# rev_D.net
KiCad netlist of a schematic drawn in EAGLE
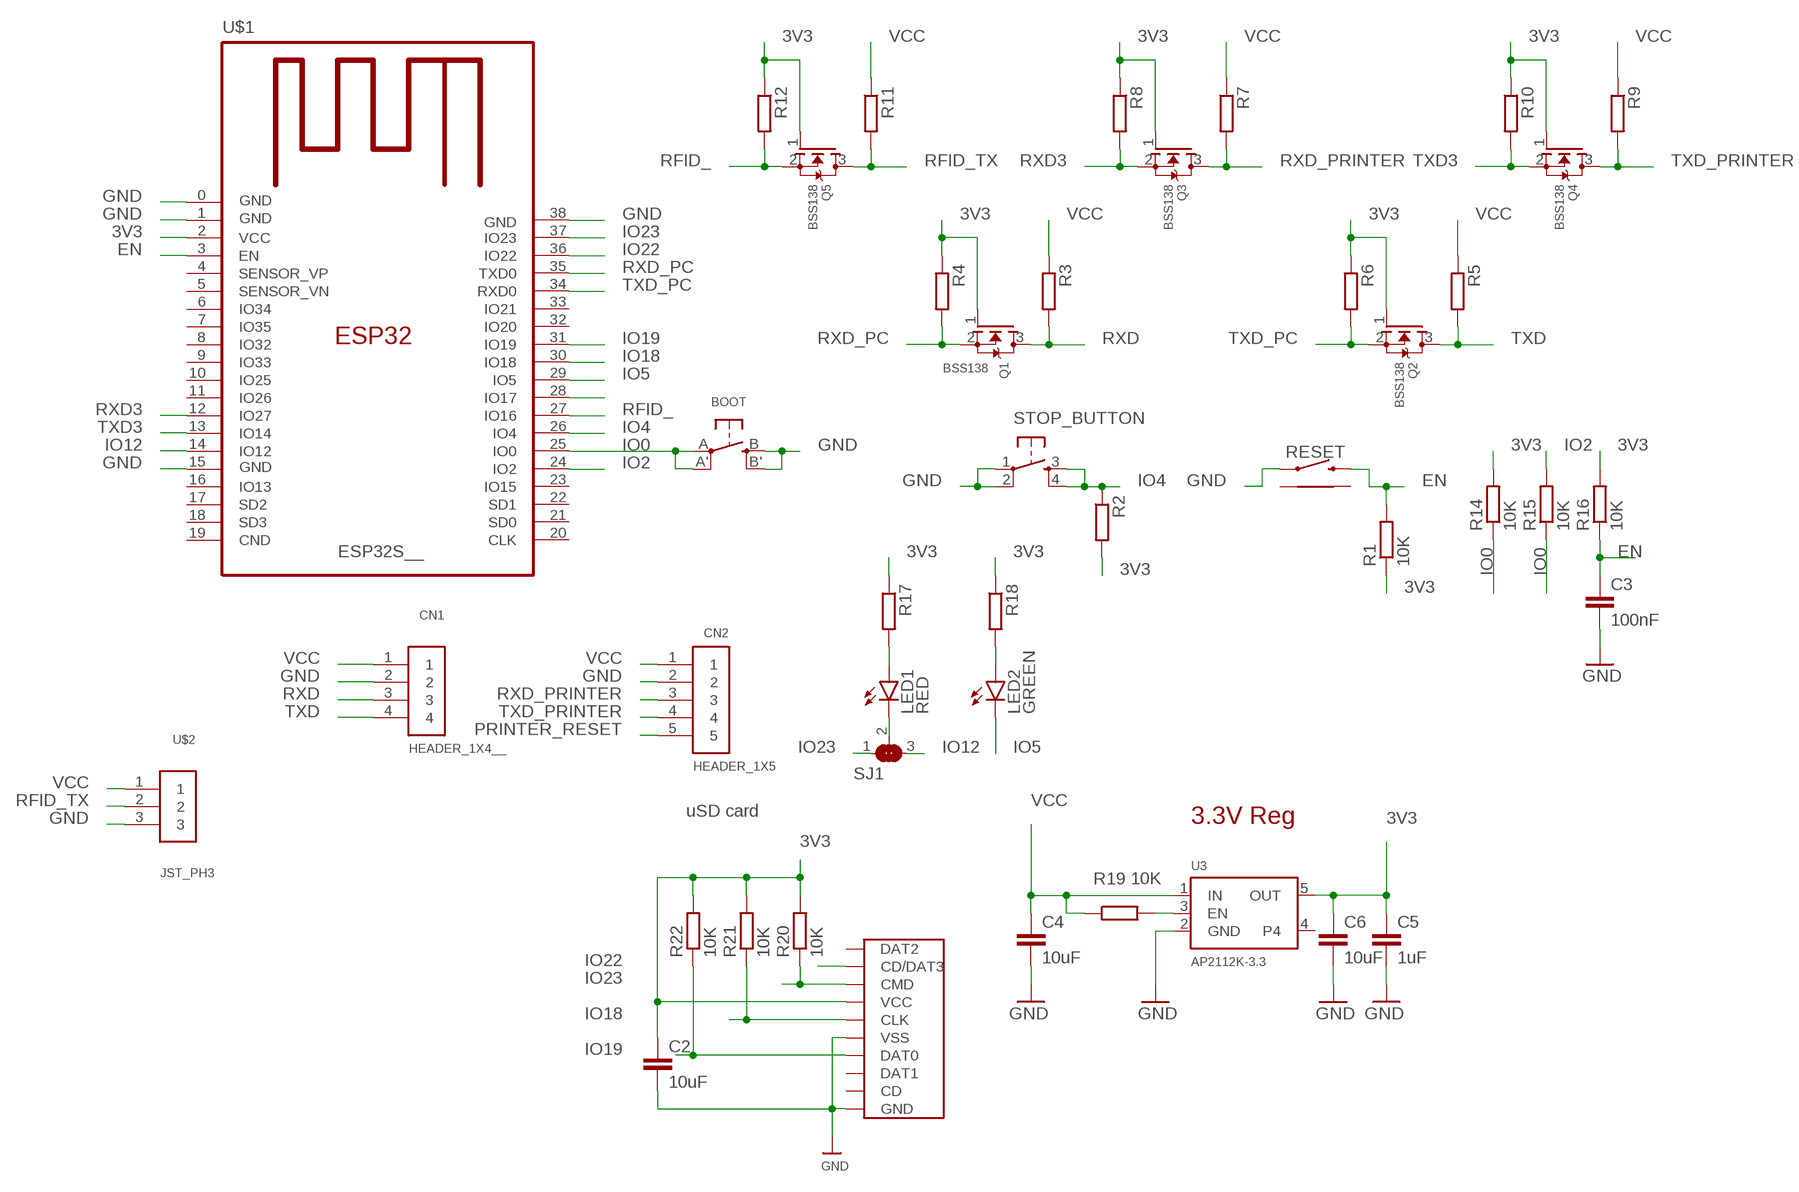
[diagram p0: schematic, sheet 1]

(export (version "E")
  (design (tool "Eeschema 10.0.6"))
  (components
    (comp (ref "BOOT")
      (value "BUTTON_KMR2_4.6X2.8")
      (footprint "eagle-import:BUTTON_KMR2_4.6X2.8")
      (libsource (lib "eagle-import") (part "BUTTON_KMR2_4.6X2.8"))
    )
    (comp (ref "C2")
      (value "10uF")
      (footprint "eagle-import:C0805")
      (libsource (lib "eagle-import") (part "C-EUC0805"))
    )
    (comp (ref "C3")
      (value "100nF")
      (footprint "eagle-import:C0805")
      (libsource (lib "eagle-import") (part "C-EUC0805"))
    )
    (comp (ref "C4")
      (value "10uF")
      (footprint "eagle-import:C0805")
      (libsource (lib "eagle-import") (part "C-EUC0805"))
    )
    (comp (ref "C5")
      (value "1uF")
      (footprint "eagle-import:C0805")
      (libsource (lib "eagle-import") (part "C-EUC0805"))
    )
    (comp (ref "C6")
      (value "10uF")
      (footprint "eagle-import:C0805")
      (libsource (lib "eagle-import") (part "C-EUC0805"))
    )
    (comp (ref "CN1")
      (value "HEADER_1X4__")
      (footprint "eagle-import:HEADER_1X4_RIGHT_ANGLE")
      (libsource (lib "eagle-import") (part "HEADER_1X4__"))
    )
    (comp (ref "CN2")
      (value "HEADER_1X5")
      (footprint "eagle-import:HEADER_1X5")
      (libsource (lib "eagle-import") (part "HEADER_1X5"))
    )
    (comp (ref "LED1")
      (value "RED")
      (footprint "eagle-import:CHIP-LED0805")
      (libsource (lib "eagle-import") (part "LEDCHIP-LED0805"))
    )
    (comp (ref "LED2")
      (value "GREEN")
      (footprint "eagle-import:CHIP-LED0805")
      (libsource (lib "eagle-import") (part "LEDCHIP-LED0805"))
    )
    (comp (ref "Q1")
      (value "BSS138")
      (footprint "eagle-import:SOT95P240X110-3")
      (libsource (lib "eagle-import") (part "MOSFET_N_"))
    )
    (comp (ref "Q2")
      (value "BSS138")
      (footprint "eagle-import:SOT95P240X110-3")
      (libsource (lib "eagle-import") (part "MOSFET_N_"))
    )
    (comp (ref "Q3")
      (value "BSS138")
      (footprint "eagle-import:SOT95P240X110-3")
      (libsource (lib "eagle-import") (part "MOSFET_N_"))
    )
    (comp (ref "Q4")
      (value "BSS138")
      (footprint "eagle-import:SOT95P240X110-3")
      (libsource (lib "eagle-import") (part "MOSFET_N_"))
    )
    (comp (ref "Q5")
      (value "BSS138")
      (footprint "eagle-import:SOT95P240X110-3")
      (libsource (lib "eagle-import") (part "MOSFET_N_"))
    )
    (comp (ref "R1")
      (value "10K")
      (footprint "eagle-import:R0805")
      (libsource (lib "eagle-import") (part "R-EU_R0805"))
    )
    (comp (ref "R2")
      (value "10K")
      (footprint "eagle-import:R0805")
      (libsource (lib "eagle-import") (part "R-EU_R0805"))
    )
    (comp (ref "R3")
      (value "10K")
      (footprint "eagle-import:R0805")
      (libsource (lib "eagle-import") (part "R-EU_R0805"))
    )
    (comp (ref "R4")
      (value "10K")
      (footprint "eagle-import:R0805")
      (libsource (lib "eagle-import") (part "R-EU_R0805"))
    )
    (comp (ref "R5")
      (value "10K")
      (footprint "eagle-import:R0805")
      (libsource (lib "eagle-import") (part "R-EU_R0805"))
    )
    (comp (ref "R6")
      (value "10K")
      (footprint "eagle-import:R0805")
      (libsource (lib "eagle-import") (part "R-EU_R0805"))
    )
    (comp (ref "R7")
      (value "10K")
      (footprint "eagle-import:R0805")
      (libsource (lib "eagle-import") (part "R-EU_R0805"))
    )
    (comp (ref "R8")
      (value "10K")
      (footprint "eagle-import:R0805")
      (libsource (lib "eagle-import") (part "R-EU_R0805"))
    )
    (comp (ref "R9")
      (value "10K")
      (footprint "eagle-import:R0805")
      (libsource (lib "eagle-import") (part "R-EU_R0805"))
    )
    (comp (ref "R10")
      (value "10K")
      (footprint "eagle-import:R0805")
      (libsource (lib "eagle-import") (part "R-EU_R0805"))
    )
    (comp (ref "R11")
      (value "10K")
      (footprint "eagle-import:R0805")
      (libsource (lib "eagle-import") (part "R-EU_R0805"))
    )
    (comp (ref "R12")
      (value "10K")
      (footprint "eagle-import:R0805")
      (libsource (lib "eagle-import") (part "R-EU_R0805"))
    )
    (comp (ref "R14")
      (value "10K")
      (footprint "eagle-import:R0805")
      (libsource (lib "eagle-import") (part "R-EU_R0805"))
    )
    (comp (ref "R15")
      (value "10K")
      (footprint "eagle-import:R0805")
      (libsource (lib "eagle-import") (part "R-EU_R0805"))
    )
    (comp (ref "R16")
      (value "10K")
      (footprint "eagle-import:R0805")
      (libsource (lib "eagle-import") (part "R-EU_R0805"))
    )
    (comp (ref "R17")
      (value "470R")
      (footprint "eagle-import:R0805")
      (libsource (lib "eagle-import") (part "R-EU_R0805"))
    )
    (comp (ref "R18")
      (value "470R")
      (footprint "eagle-import:R0805")
      (libsource (lib "eagle-import") (part "R-EU_R0805"))
    )
    (comp (ref "R19")
      (value "10K")
      (footprint "eagle-import:R0805")
      (libsource (lib "eagle-import") (part "R-EU_R0805"))
    )
    (comp (ref "R20")
      (value "10K")
      (footprint "eagle-import:R0805")
      (libsource (lib "eagle-import") (part "R-EU_R0805"))
    )
    (comp (ref "R21")
      (value "10K")
      (footprint "eagle-import:R0805")
      (libsource (lib "eagle-import") (part "R-EU_R0805"))
    )
    (comp (ref "R22")
      (value "10K")
      (footprint "eagle-import:R0805")
      (libsource (lib "eagle-import") (part "R-EU_R0805"))
    )
    (comp (ref "RESET")
      (value "TACTILE_SWITCH_RIGHT_ANGLE_THT_")
      (footprint "eagle-import:TACTILE_SWITCH_RIGHT_ANGLE_THT")
      (libsource (lib "eagle-import") (part "TACTILE_SWITCH_RIGHT_ANGLE_THT_"))
    )
    (comp (ref "SD_CARD")
      (value "MICRO_SD_CARD_")
      (footprint "eagle-import:TFP09-2--12B")
      (libsource (lib "eagle-import") (part "MICRO_SD_CARD_"))
    )
    (comp (ref "SJ1")
      (value "SOLDERJUMPER_2WAY0805")
      (footprint "eagle-import:SOLDERJUMPER_2WAY_OPEN_0805")
      (libsource (lib "eagle-import") (part "SOLDERJUMPER_2WAY0805"))
    )
    (comp (ref "STOP_BUTTON")
      (value "TACTILE_SWITCH_LONG_THT_")
      (footprint "eagle-import:TACTILE_SWICTH_THT")
      (libsource (lib "eagle-import") (part "TACTILE_SWITCH_LONG_THT_"))
    )
    (comp (ref "U$1")
      (value "ESP32S__")
      (footprint "eagle-import:ESP32S")
      (libsource (lib "eagle-import") (part "ESP32S__"))
    )
    (comp (ref "U$2")
      (value "JST_PH3")
      (footprint "eagle-import:JST-PH3")
      (libsource (lib "eagle-import") (part "JST_PH3"))
    )
    (comp (ref "U3")
      (value "AP2112K-3.3")
      (footprint "eagle-import:SOT95P290X120-5")
      (libsource (lib "eagle-import") (part "AP2112K-3.3_"))
    )
  )
  (nets
    (net (code "1") (name "/3V3") (class "Default")
      (node (ref "C2") (pin "1") (pinfunction "1_1") (pintype "passive"))
      (node (ref "C5") (pin "1") (pinfunction "1_1") (pintype "passive"))
      (node (ref "C6") (pin "1") (pinfunction "1_1") (pintype "passive"))
      (node (ref "Q1") (pin "1") (pinfunction "G_1") (pintype "bidirectional"))
      (node (ref "Q2") (pin "1") (pinfunction "G_1") (pintype "bidirectional"))
      (node (ref "Q3") (pin "1") (pinfunction "G_1") (pintype "bidirectional"))
      (node (ref "Q4") (pin "1") (pinfunction "G_1") (pintype "bidirectional"))
      (node (ref "Q5") (pin "1") (pinfunction "G_1") (pintype "bidirectional"))
      (node (ref "R1") (pin "1") (pinfunction "1_1") (pintype "passive"))
      (node (ref "R10") (pin "1") (pinfunction "1_1") (pintype "passive"))
      (node (ref "R12") (pin "1") (pinfunction "1_1") (pintype "passive"))
      (node (ref "R14") (pin "2") (pinfunction "2_2") (pintype "passive"))
      (node (ref "R16") (pin "2") (pinfunction "2_2") (pintype "passive"))
      (node (ref "R17") (pin "1") (pinfunction "1_1") (pintype "passive"))
      (node (ref "R18") (pin "1") (pinfunction "1_1") (pintype "passive"))
      (node (ref "R2") (pin "2") (pinfunction "2_2") (pintype "passive"))
      (node (ref "R20") (pin "2") (pinfunction "2_2") (pintype "passive"))
      (node (ref "R21") (pin "2") (pinfunction "2_2") (pintype "passive"))
      (node (ref "R22") (pin "2") (pinfunction "2_2") (pintype "passive"))
      (node (ref "R4") (pin "1") (pinfunction "1_1") (pintype "passive"))
      (node (ref "R6") (pin "1") (pinfunction "1_1") (pintype "passive"))
      (node (ref "R8") (pin "1") (pinfunction "1_1") (pintype "passive"))
      (node (ref "SD_CARD") (pin "VCC") (pinfunction "VCC_VCC") (pintype "bidirectional"))
      (node (ref "U$1") (pin "2") (pinfunction "VCC_2") (pintype "power_in"))
      (node (ref "U3") (pin "5") (pinfunction "OUT_5") (pintype "bidirectional"))
    )
    (net (code "2") (name "/EN") (class "Default")
      (node (ref "C3") (pin "1") (pinfunction "1_1") (pintype "passive"))
      (node (ref "R1") (pin "2") (pinfunction "2_2") (pintype "passive"))
      (node (ref "R16") (pin "1") (pinfunction "1_1") (pintype "passive"))
      (node (ref "RESET") (pin "2") (pinfunction "2_2") (pintype "passive"))
      (node (ref "U$1") (pin "3") (pinfunction "EN_3") (pintype "bidirectional"))
    )
    (net (code "3") (name "/IO0") (class "Default")
      (node (ref "BOOT") (pin "A") (pinfunction "P_A") (pintype "passive"))
      (node (ref "BOOT") (pin "A'") (pinfunction "P1_A'") (pintype "passive"))
      (node (ref "R14") (pin "1") (pinfunction "1_1") (pintype "passive"))
      (node (ref "R15") (pin "1") (pinfunction "1_1") (pintype "passive"))
      (node (ref "U$1") (pin "25") (pinfunction "IO0_25") (pintype "bidirectional"))
    )
    (net (code "4") (name "/IO2") (class "Default")
      (node (ref "R15") (pin "2") (pinfunction "2_2") (pintype "passive"))
      (node (ref "U$1") (pin "24") (pinfunction "IO2_24") (pintype "bidirectional"))
    )
    (net (code "5") (name "/IO4") (class "Default")
      (node (ref "R2") (pin "1") (pinfunction "1_1") (pintype "passive"))
      (node (ref "STOP_BUTTON") (pin "3") (pinfunction "3_3") (pintype "passive"))
      (node (ref "STOP_BUTTON") (pin "4") (pinfunction "4_4") (pintype "passive"))
      (node (ref "U$1") (pin "26") (pinfunction "IO4_26") (pintype "bidirectional"))
    )
    (net (code "6") (name "/IO5") (class "Default")
      (node (ref "LED2") (pin "C") (pinfunction "C_C") (pintype "passive"))
      (node (ref "U$1") (pin "29") (pinfunction "IO5_29") (pintype "bidirectional"))
    )
    (net (code "7") (name "/IO12") (class "Default")
      (node (ref "SJ1") (pin "3") (pinfunction "3_3") (pintype "passive"))
      (node (ref "U$1") (pin "14") (pinfunction "IO12_14") (pintype "bidirectional"))
    )
    (net (code "8") (name "/IO18") (class "Default")
      (node (ref "R21") (pin "1") (pinfunction "1_1") (pintype "passive"))
      (node (ref "SD_CARD") (pin "CLK") (pinfunction "CLK_CLK") (pintype "bidirectional"))
      (node (ref "U$1") (pin "30") (pinfunction "IO18_30") (pintype "bidirectional"))
    )
    (net (code "9") (name "/IO19") (class "Default")
      (node (ref "R22") (pin "1") (pinfunction "1_1") (pintype "passive"))
      (node (ref "SD_CARD") (pin "DAT0") (pinfunction "DAT0_DAT0") (pintype "bidirectional"))
      (node (ref "U$1") (pin "31") (pinfunction "IO19_31") (pintype "bidirectional"))
    )
    (net (code "10") (name "/IO22") (class "Default")
      (node (ref "SD_CARD") (pin "CD/DAT3") (pinfunction "CD/DAT3_CD/DAT3") (pintype "bidirectional"))
      (node (ref "U$1") (pin "36") (pinfunction "IO22_36") (pintype "bidirectional"))
    )
    (net (code "11") (name "/IO23") (class "Default")
      (node (ref "R20") (pin "1") (pinfunction "1_1") (pintype "passive"))
      (node (ref "SD_CARD") (pin "CMD") (pinfunction "CMD_CMD") (pintype "bidirectional"))
      (node (ref "SJ1") (pin "1") (pinfunction "1_1") (pintype "passive"))
      (node (ref "U$1") (pin "37") (pinfunction "IO23_37") (pintype "bidirectional"))
    )
    (net (code "12") (name "/PRINTER_RESET") (class "Default")
      (node (ref "CN2") (pin "5") (pinfunction "5_5") (pintype "bidirectional"))
    )
    (net (code "13") (name "/RFID_") (class "Default")
      (node (ref "Q5") (pin "2") (pinfunction "S_2") (pintype "bidirectional"))
      (node (ref "R12") (pin "2") (pinfunction "2_2") (pintype "passive"))
      (node (ref "U$1") (pin "27") (pinfunction "IO16_27") (pintype "bidirectional"))
    )
    (net (code "14") (name "/RFID_TX") (class "Default")
      (node (ref "Q5") (pin "3") (pinfunction "D_3") (pintype "bidirectional"))
      (node (ref "R11") (pin "2") (pinfunction "2_2") (pintype "passive"))
      (node (ref "U$2") (pin "2") (pinfunction "2_2") (pintype "bidirectional"))
    )
    (net (code "15") (name "/RXD") (class "Default")
      (node (ref "CN1") (pin "3") (pinfunction "3_3") (pintype "bidirectional"))
      (node (ref "Q1") (pin "3") (pinfunction "D_3") (pintype "bidirectional"))
      (node (ref "R3") (pin "2") (pinfunction "2_2") (pintype "passive"))
    )
    (net (code "16") (name "/RXD3") (class "Default")
      (node (ref "Q3") (pin "2") (pinfunction "S_2") (pintype "bidirectional"))
      (node (ref "R8") (pin "2") (pinfunction "2_2") (pintype "passive"))
      (node (ref "U$1") (pin "12") (pinfunction "IO27_12") (pintype "bidirectional"))
    )
    (net (code "17") (name "/RXD_PC") (class "Default")
      (node (ref "Q1") (pin "2") (pinfunction "S_2") (pintype "bidirectional"))
      (node (ref "R4") (pin "2") (pinfunction "2_2") (pintype "passive"))
      (node (ref "U$1") (pin "35") (pinfunction "TXD0_35") (pintype "bidirectional"))
    )
    (net (code "18") (name "/RXD_PRINTER") (class "Default")
      (node (ref "CN2") (pin "3") (pinfunction "3_3") (pintype "bidirectional"))
      (node (ref "Q3") (pin "3") (pinfunction "D_3") (pintype "bidirectional"))
      (node (ref "R7") (pin "2") (pinfunction "2_2") (pintype "passive"))
    )
    (net (code "19") (name "/TXD") (class "Default")
      (node (ref "CN1") (pin "4") (pinfunction "4_4") (pintype "bidirectional"))
      (node (ref "Q2") (pin "3") (pinfunction "D_3") (pintype "bidirectional"))
      (node (ref "R5") (pin "2") (pinfunction "2_2") (pintype "passive"))
    )
    (net (code "20") (name "/TXD3") (class "Default")
      (node (ref "Q4") (pin "2") (pinfunction "S_2") (pintype "bidirectional"))
      (node (ref "R10") (pin "2") (pinfunction "2_2") (pintype "passive"))
      (node (ref "U$1") (pin "13") (pinfunction "IO14_13") (pintype "bidirectional"))
    )
    (net (code "21") (name "/TXD_PC") (class "Default")
      (node (ref "Q2") (pin "2") (pinfunction "S_2") (pintype "bidirectional"))
      (node (ref "R6") (pin "2") (pinfunction "2_2") (pintype "passive"))
      (node (ref "U$1") (pin "34") (pinfunction "RXD0_34") (pintype "bidirectional"))
    )
    (net (code "22") (name "/TXD_PRINTER") (class "Default")
      (node (ref "CN2") (pin "4") (pinfunction "4_4") (pintype "bidirectional"))
      (node (ref "Q4") (pin "3") (pinfunction "D_3") (pintype "bidirectional"))
      (node (ref "R9") (pin "2") (pinfunction "2_2") (pintype "passive"))
    )
    (net (code "23") (name "/VCC") (class "Default")
      (node (ref "C4") (pin "1") (pinfunction "1_1") (pintype "passive"))
      (node (ref "CN1") (pin "1") (pinfunction "1_1") (pintype "bidirectional"))
      (node (ref "CN2") (pin "1") (pinfunction "1_1") (pintype "bidirectional"))
      (node (ref "R11") (pin "1") (pinfunction "1_1") (pintype "passive"))
      (node (ref "R19") (pin "1") (pinfunction "1_1") (pintype "passive"))
      (node (ref "R3") (pin "1") (pinfunction "1_1") (pintype "passive"))
      (node (ref "R5") (pin "1") (pinfunction "1_1") (pintype "passive"))
      (node (ref "R7") (pin "1") (pinfunction "1_1") (pintype "passive"))
      (node (ref "R9") (pin "1") (pinfunction "1_1") (pintype "passive"))
      (node (ref "U$2") (pin "1") (pinfunction "1_1") (pintype "bidirectional"))
      (node (ref "U3") (pin "1") (pinfunction "IN_1") (pintype "bidirectional"))
    )
    (net (code "24") (name "GND") (class "Default")
      (node (ref "BOOT") (pin "B") (pinfunction "S_B") (pintype "passive"))
      (node (ref "BOOT") (pin "B'") (pinfunction "S1_B'") (pintype "passive"))
      (node (ref "C2") (pin "2") (pinfunction "2_2") (pintype "passive"))
      (node (ref "C3") (pin "2") (pinfunction "2_2") (pintype "passive"))
      (node (ref "C4") (pin "2") (pinfunction "2_2") (pintype "passive"))
      (node (ref "C5") (pin "2") (pinfunction "2_2") (pintype "passive"))
      (node (ref "C6") (pin "2") (pinfunction "2_2") (pintype "passive"))
      (node (ref "CN1") (pin "2") (pinfunction "2_2") (pintype "bidirectional"))
      (node (ref "CN2") (pin "2") (pinfunction "2_2") (pintype "bidirectional"))
      (node (ref "RESET") (pin "1") (pinfunction "1_1") (pintype "passive"))
      (node (ref "SD_CARD") (pin "GND") (pinfunction "GND_GND") (pintype "bidirectional"))
      (node (ref "SD_CARD") (pin "GND@1") (pinfunction "GND_GND@1") (pintype "bidirectional"))
      (node (ref "SD_CARD") (pin "GND@2") (pinfunction "GND_GND@2") (pintype "bidirectional"))
      (node (ref "SD_CARD") (pin "GND@3") (pinfunction "VSS_GND@3") (pintype "bidirectional"))
      (node (ref "SD_CARD") (pin "VSS") (pinfunction "GND_VSS") (pintype "bidirectional"))
      (node (ref "STOP_BUTTON") (pin "1") (pinfunction "1_1") (pintype "passive"))
      (node (ref "STOP_BUTTON") (pin "2") (pinfunction "2_2") (pintype "passive"))
      (node (ref "U$1") (pin "0") (pinfunction "GND_0") (pintype "power_in"))
      (node (ref "U$1") (pin "1") (pinfunction "GND_1") (pintype "power_in"))
      (node (ref "U$1") (pin "15") (pinfunction "GND_15") (pintype "power_in"))
      (node (ref "U$1") (pin "38") (pinfunction "GND_38") (pintype "power_in"))
      (node (ref "U$2") (pin "3") (pinfunction "3_3") (pintype "bidirectional"))
      (node (ref "U3") (pin "2") (pinfunction "GND_2") (pintype "bidirectional"))
    )
    (net (code "25") (name "Net-(LED1-PadA)") (class "Default")
      (node (ref "LED1") (pin "A") (pinfunction "A_A") (pintype "passive"))
      (node (ref "R17") (pin "2") (pinfunction "2_2") (pintype "passive"))
    )
    (net (code "26") (name "Net-(LED1-PadC)") (class "Default")
      (node (ref "LED1") (pin "C") (pinfunction "C_C") (pintype "passive"))
      (node (ref "SJ1") (pin "2") (pinfunction "2_2") (pintype "passive"))
    )
    (net (code "27") (name "Net-(LED2-PadA)") (class "Default")
      (node (ref "LED2") (pin "A") (pinfunction "A_A") (pintype "passive"))
      (node (ref "R18") (pin "2") (pinfunction "2_2") (pintype "passive"))
    )
    (net (code "28") (name "Net-(U3-EN)") (class "Default")
      (node (ref "R19") (pin "2") (pinfunction "2_2") (pintype "passive"))
      (node (ref "U3") (pin "3") (pinfunction "EN_3") (pintype "bidirectional"))
    )
    (net (code "29") (name "unconnected-(RESET-3-PadANCHOR1)") (class "Default")
      (node (ref "RESET") (pin "ANCHOR1") (pinfunction "3_ANCHOR1") (pintype "passive"))
    )
    (net (code "30") (name "unconnected-(RESET-4-PadANCHOR2)") (class "Default")
      (node (ref "RESET") (pin "ANCHOR2") (pinfunction "4_ANCHOR2") (pintype "passive"))
    )
    (net (code "31") (name "unconnected-(SD_CARD-PadCD)") (class "Default")
      (node (ref "SD_CARD") (pin "CD") (pinfunction "CD_CD") (pintype "bidirectional"))
    )
    (net (code "32") (name "unconnected-(SD_CARD-PadDAT1)") (class "Default")
      (node (ref "SD_CARD") (pin "DAT1") (pinfunction "DAT1_DAT1") (pintype "bidirectional"))
    )
    (net (code "33") (name "unconnected-(SD_CARD-PadDAT2)") (class "Default")
      (node (ref "SD_CARD") (pin "DAT2") (pinfunction "DAT2_DAT2") (pintype "bidirectional"))
    )
    (net (code "34") (name "unconnected-(U$1-CLK-Pad20)") (class "Default")
      (node (ref "U$1") (pin "20") (pinfunction "CLK_20") (pintype "bidirectional"))
    )
    (net (code "35") (name "unconnected-(U$1-CND-Pad19)") (class "Default")
      (node (ref "U$1") (pin "19") (pinfunction "CND_19") (pintype "bidirectional"))
    )
    (net (code "36") (name "unconnected-(U$1-IO13-Pad16)") (class "Default")
      (node (ref "U$1") (pin "16") (pinfunction "IO13_16") (pintype "bidirectional"))
    )
    (net (code "37") (name "unconnected-(U$1-IO15-Pad23)") (class "Default")
      (node (ref "U$1") (pin "23") (pinfunction "IO15_23") (pintype "bidirectional"))
    )
    (net (code "38") (name "unconnected-(U$1-IO17-Pad28)") (class "Default")
      (node (ref "U$1") (pin "28") (pinfunction "IO17_28") (pintype "bidirectional"))
    )
    (net (code "39") (name "unconnected-(U$1-IO20-Pad32)") (class "Default")
      (node (ref "U$1") (pin "32") (pinfunction "IO20_32") (pintype "bidirectional"))
    )
    (net (code "40") (name "unconnected-(U$1-IO21-Pad33)") (class "Default")
      (node (ref "U$1") (pin "33") (pinfunction "IO21_33") (pintype "bidirectional"))
    )
    (net (code "41") (name "unconnected-(U$1-IO25-Pad10)") (class "Default")
      (node (ref "U$1") (pin "10") (pinfunction "IO25_10") (pintype "bidirectional"))
    )
    (net (code "42") (name "unconnected-(U$1-IO26-Pad11)") (class "Default")
      (node (ref "U$1") (pin "11") (pinfunction "IO26_11") (pintype "bidirectional"))
    )
    (net (code "43") (name "unconnected-(U$1-IO32-Pad8)") (class "Default")
      (node (ref "U$1") (pin "8") (pinfunction "IO32_8") (pintype "bidirectional"))
    )
    (net (code "44") (name "unconnected-(U$1-IO33-Pad9)") (class "Default")
      (node (ref "U$1") (pin "9") (pinfunction "IO33_9") (pintype "bidirectional"))
    )
    (net (code "45") (name "unconnected-(U$1-IO34-Pad6)") (class "Default")
      (node (ref "U$1") (pin "6") (pinfunction "IO34_6") (pintype "bidirectional"))
    )
    (net (code "46") (name "unconnected-(U$1-IO35-Pad7)") (class "Default")
      (node (ref "U$1") (pin "7") (pinfunction "IO35_7") (pintype "bidirectional"))
    )
    (net (code "47") (name "unconnected-(U$1-SD0-Pad21)") (class "Default")
      (node (ref "U$1") (pin "21") (pinfunction "SD0_21") (pintype "bidirectional"))
    )
    (net (code "48") (name "unconnected-(U$1-SD1-Pad22)") (class "Default")
      (node (ref "U$1") (pin "22") (pinfunction "SD1_22") (pintype "bidirectional"))
    )
    (net (code "49") (name "unconnected-(U$1-SD2-Pad17)") (class "Default")
      (node (ref "U$1") (pin "17") (pinfunction "SD2_17") (pintype "bidirectional"))
    )
    (net (code "50") (name "unconnected-(U$1-SD3-Pad18)") (class "Default")
      (node (ref "U$1") (pin "18") (pinfunction "SD3_18") (pintype "bidirectional"))
    )
    (net (code "51") (name "unconnected-(U$1-SENSOR_VN-Pad5)") (class "Default")
      (node (ref "U$1") (pin "5") (pinfunction "SENSOR_VN_5") (pintype "bidirectional"))
    )
    (net (code "52") (name "unconnected-(U$1-SENSOR_VP-Pad4)") (class "Default")
      (node (ref "U$1") (pin "4") (pinfunction "SENSOR_VP_4") (pintype "bidirectional"))
    )
    (net (code "53") (name "unconnected-(U3-P4-Pad4)") (class "Default")
      (node (ref "U3") (pin "4") (pinfunction "P4_4") (pintype "bidirectional"))
    )
  )
)
